# picoxcvr.net
KiCad netlist of a schematic drawn in EAGLE
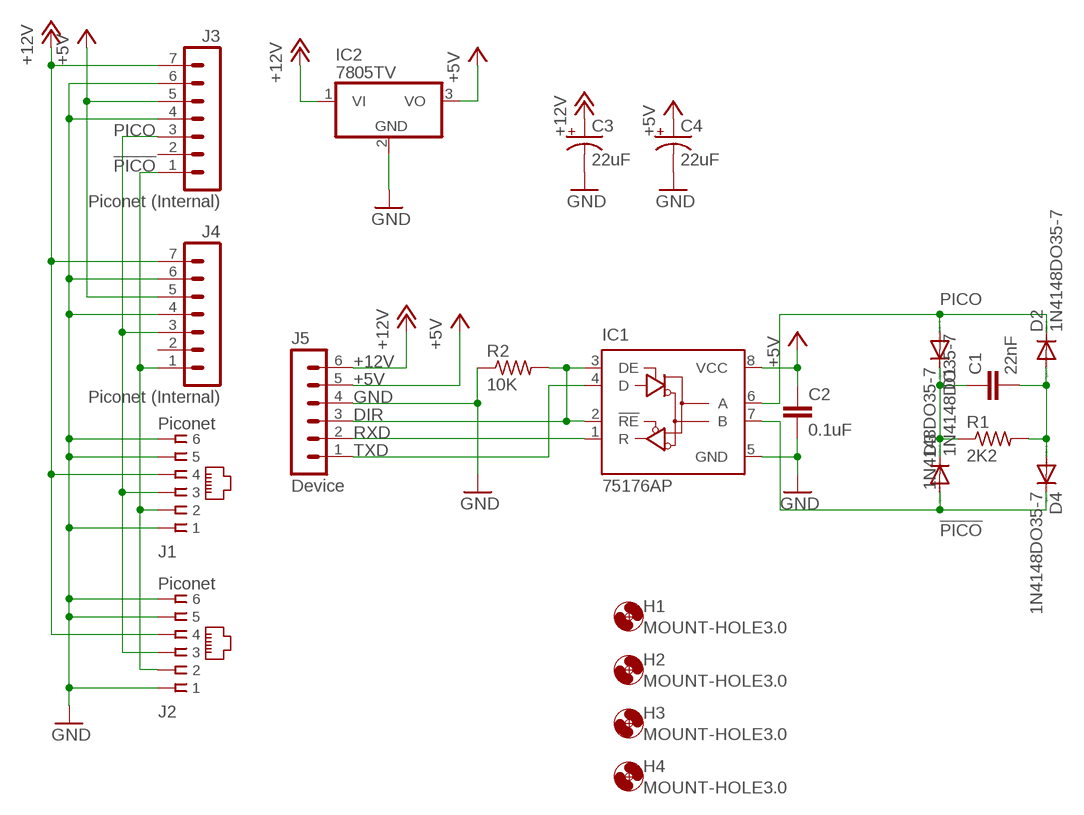
[diagram p0: schematic, sheet 1]

(export (version "E")
  (design (tool "Eeschema 10.0.6"))
  (components
    (comp (ref "C1")
      (value "22nF")
      (footprint "eagle-import:C050-024X044")
      (libsource (lib "eagle-import") (part "C-EU050-024X044"))
    )
    (comp (ref "C2")
      (value "0.1uF")
      (footprint "eagle-import:C050-024X044")
      (libsource (lib "eagle-import") (part "C-EU050-024X044"))
    )
    (comp (ref "C3")
      (value "22uF")
      (footprint "eagle-import:E2,5-6")
      (libsource (lib "eagle-import") (part "CPOL-USE2.5-6"))
    )
    (comp (ref "C4")
      (value "22uF")
      (footprint "eagle-import:E2,5-6")
      (libsource (lib "eagle-import") (part "CPOL-USE2.5-6"))
    )
    (comp (ref "D1")
      (value "1N4148DO35-7")
      (footprint "eagle-import:DO35-7")
      (libsource (lib "eagle-import") (part "1N4148DO35-7"))
    )
    (comp (ref "D2")
      (value "1N4148DO35-7")
      (footprint "eagle-import:DO35-7")
      (libsource (lib "eagle-import") (part "1N4148DO35-7"))
    )
    (comp (ref "D3")
      (value "1N4148DO35-7")
      (footprint "eagle-import:DO35-7")
      (libsource (lib "eagle-import") (part "1N4148DO35-7"))
    )
    (comp (ref "D4")
      (value "1N4148DO35-7")
      (footprint "eagle-import:DO35-7")
      (libsource (lib "eagle-import") (part "1N4148DO35-7"))
    )
    (comp (ref "H1")
      (value "MOUNT-HOLE3.0")
      (footprint "eagle-import:3,0")
      (libsource (lib "eagle-import") (part "MOUNT-HOLE3.0"))
    )
    (comp (ref "H2")
      (value "MOUNT-HOLE3.0")
      (footprint "eagle-import:3,0")
      (libsource (lib "eagle-import") (part "MOUNT-HOLE3.0"))
    )
    (comp (ref "H3")
      (value "MOUNT-HOLE3.0")
      (footprint "eagle-import:3,0")
      (libsource (lib "eagle-import") (part "MOUNT-HOLE3.0"))
    )
    (comp (ref "H4")
      (value "MOUNT-HOLE3.0")
      (footprint "eagle-import:3,0")
      (libsource (lib "eagle-import") (part "MOUNT-HOLE3.0"))
    )
    (comp (ref "IC1")
      (value "75176AP")
      (footprint "eagle-import:DIL08")
      (libsource (lib "eagle-import") (part "75176AP"))
    )
    (comp (ref "IC2")
      (value "7805TV")
      (footprint "eagle-import:TO220V")
      (libsource (lib "eagle-import") (part "78TV05"))
    )
    (comp (ref "J1")
      (value "Piconet")
      (footprint "eagle-import:RJ11-NO_SHIELD")
      (libsource (lib "eagle-import") (part "RJ11-2X"))
    )
    (comp (ref "J2")
      (value "Piconet")
      (footprint "eagle-import:RJ11-NO_SHIELD")
      (libsource (lib "eagle-import") (part "RJ11-2X"))
    )
    (comp (ref "J3")
      (value "Piconet (Internal)")
      (footprint "eagle-import:MA07-1")
      (libsource (lib "eagle-import") (part "MA07-1"))
    )
    (comp (ref "J4")
      (value "Piconet (Internal)")
      (footprint "eagle-import:MA07-1")
      (libsource (lib "eagle-import") (part "MA07-1"))
    )
    (comp (ref "J5")
      (value "Device")
      (footprint "eagle-import:MA06-1")
      (libsource (lib "eagle-import") (part "MA06-1"))
    )
    (comp (ref "R1")
      (value "2K2")
      (footprint "eagle-import:0204_7")
      (libsource (lib "eagle-import") (part "R-US_0204/7"))
    )
    (comp (ref "R2")
      (value "10K")
      (footprint "eagle-import:0204_7")
      (libsource (lib "eagle-import") (part "R-US_0204/7"))
    )
  )
  (nets
    (net (code "1") (name "+5V") (class "Default")
      (node (ref "C2") (pin "1") (pinfunction "1_1") (pintype "passive"))
      (node (ref "C4") (pin "+") (pinfunction "+_+") (pintype "passive"))
      (node (ref "IC1") (pin "8") (pinfunction "VCC_8") (pintype "power_in"))
      (node (ref "IC2") (pin "3") (pinfunction "VO_3") (pintype "passive"))
      (node (ref "J3") (pin "5") (pinfunction "5_5") (pintype "passive"))
      (node (ref "J4") (pin "5") (pinfunction "5_5") (pintype "passive"))
      (node (ref "J5") (pin "5") (pinfunction "5_5") (pintype "passive"))
    )
    (net (code "2") (name "+12V") (class "Default")
      (node (ref "C3") (pin "+") (pinfunction "+_+") (pintype "passive"))
      (node (ref "IC2") (pin "1") (pinfunction "VI_1") (pintype "input"))
      (node (ref "J1") (pin "4") (pinfunction "4_4") (pintype "passive"))
      (node (ref "J2") (pin "4") (pinfunction "4_4") (pintype "passive"))
      (node (ref "J3") (pin "7") (pinfunction "7_7") (pintype "passive"))
      (node (ref "J4") (pin "7") (pinfunction "7_7") (pintype "passive"))
      (node (ref "J5") (pin "6") (pinfunction "6_6") (pintype "passive"))
    )
    (net (code "3") (name "/DIR") (class "Default")
      (node (ref "IC1") (pin "2") (pinfunction "~{RE}_2") (pintype "input"))
      (node (ref "IC1") (pin "3") (pinfunction "DE_3") (pintype "input"))
      (node (ref "J5") (pin "3") (pinfunction "3_3") (pintype "passive"))
      (node (ref "R2") (pin "2") (pinfunction "2_2") (pintype "passive"))
    )
    (net (code "4") (name "/PICO") (class "Default")
      (node (ref "D1") (pin "A") (pinfunction "A_A") (pintype "passive"))
      (node (ref "D2") (pin "C") (pinfunction "C_C") (pintype "passive"))
      (node (ref "IC1") (pin "6") (pinfunction "A_6") (pintype "output"))
      (node (ref "J1") (pin "3") (pinfunction "3_3") (pintype "passive"))
      (node (ref "J2") (pin "3") (pinfunction "3_3") (pintype "passive"))
      (node (ref "J3") (pin "3") (pinfunction "3_3") (pintype "passive"))
      (node (ref "J4") (pin "3") (pinfunction "3_3") (pintype "passive"))
    )
    (net (code "5") (name "/RXD") (class "Default")
      (node (ref "IC1") (pin "1") (pinfunction "R_1") (pintype "input"))
      (node (ref "J5") (pin "2") (pinfunction "2_2") (pintype "passive"))
    )
    (net (code "6") (name "/TXD") (class "Default")
      (node (ref "IC1") (pin "4") (pinfunction "D_4") (pintype "input"))
      (node (ref "J5") (pin "1") (pinfunction "1_1") (pintype "passive"))
    )
    (net (code "7") (name "/~{PICO}") (class "Default")
      (node (ref "D3") (pin "A") (pinfunction "A_A") (pintype "passive"))
      (node (ref "D4") (pin "C") (pinfunction "C_C") (pintype "passive"))
      (node (ref "IC1") (pin "7") (pinfunction "B_7") (pintype "output"))
      (node (ref "J1") (pin "2") (pinfunction "2_2") (pintype "passive"))
      (node (ref "J2") (pin "2") (pinfunction "2_2") (pintype "passive"))
      (node (ref "J3") (pin "1") (pinfunction "1_1") (pintype "passive"))
      (node (ref "J4") (pin "1") (pinfunction "1_1") (pintype "passive"))
    )
    (net (code "8") (name "GND") (class "Default")
      (node (ref "C2") (pin "2") (pinfunction "2_2") (pintype "passive"))
      (node (ref "C3") (pin "-") (pinfunction "-_-") (pintype "passive"))
      (node (ref "C4") (pin "-") (pinfunction "-_-") (pintype "passive"))
      (node (ref "IC1") (pin "5") (pinfunction "GND_5") (pintype "power_in"))
      (node (ref "IC2") (pin "2") (pinfunction "GND_2") (pintype "passive"))
      (node (ref "J1") (pin "1") (pinfunction "1_1") (pintype "passive"))
      (node (ref "J1") (pin "5") (pinfunction "5_5") (pintype "passive"))
      (node (ref "J1") (pin "6") (pinfunction "6_6") (pintype "passive"))
      (node (ref "J2") (pin "1") (pinfunction "1_1") (pintype "passive"))
      (node (ref "J2") (pin "5") (pinfunction "5_5") (pintype "passive"))
      (node (ref "J2") (pin "6") (pinfunction "6_6") (pintype "passive"))
      (node (ref "J3") (pin "4") (pinfunction "4_4") (pintype "passive"))
      (node (ref "J3") (pin "6") (pinfunction "6_6") (pintype "passive"))
      (node (ref "J4") (pin "4") (pinfunction "4_4") (pintype "passive"))
      (node (ref "J4") (pin "6") (pinfunction "6_6") (pintype "passive"))
      (node (ref "J5") (pin "4") (pinfunction "4_4") (pintype "passive"))
      (node (ref "R2") (pin "1") (pinfunction "1_1") (pintype "passive"))
    )
    (net (code "9") (name "Net-(C1-Pad1)") (class "Default")
      (node (ref "C1") (pin "1") (pinfunction "1_1") (pintype "passive"))
      (node (ref "D1") (pin "C") (pinfunction "C_C") (pintype "passive"))
      (node (ref "D3") (pin "C") (pinfunction "C_C") (pintype "passive"))
      (node (ref "R1") (pin "1") (pinfunction "1_1") (pintype "passive"))
    )
    (net (code "10") (name "Net-(C1-Pad2)") (class "Default")
      (node (ref "C1") (pin "2") (pinfunction "2_2") (pintype "passive"))
      (node (ref "D2") (pin "A") (pinfunction "A_A") (pintype "passive"))
      (node (ref "D4") (pin "A") (pinfunction "A_A") (pintype "passive"))
      (node (ref "R1") (pin "2") (pinfunction "2_2") (pintype "passive"))
    )
    (net (code "11") (name "unconnected-(J3-Pad2)") (class "Default")
      (node (ref "J3") (pin "2") (pinfunction "2_2") (pintype "passive"))
    )
    (net (code "12") (name "unconnected-(J4-Pad2)") (class "Default")
      (node (ref "J4") (pin "2") (pinfunction "2_2") (pintype "passive"))
    )
  )
)
